# SCH.net
KiCad netlist of a schematic drawn in EasyEDA
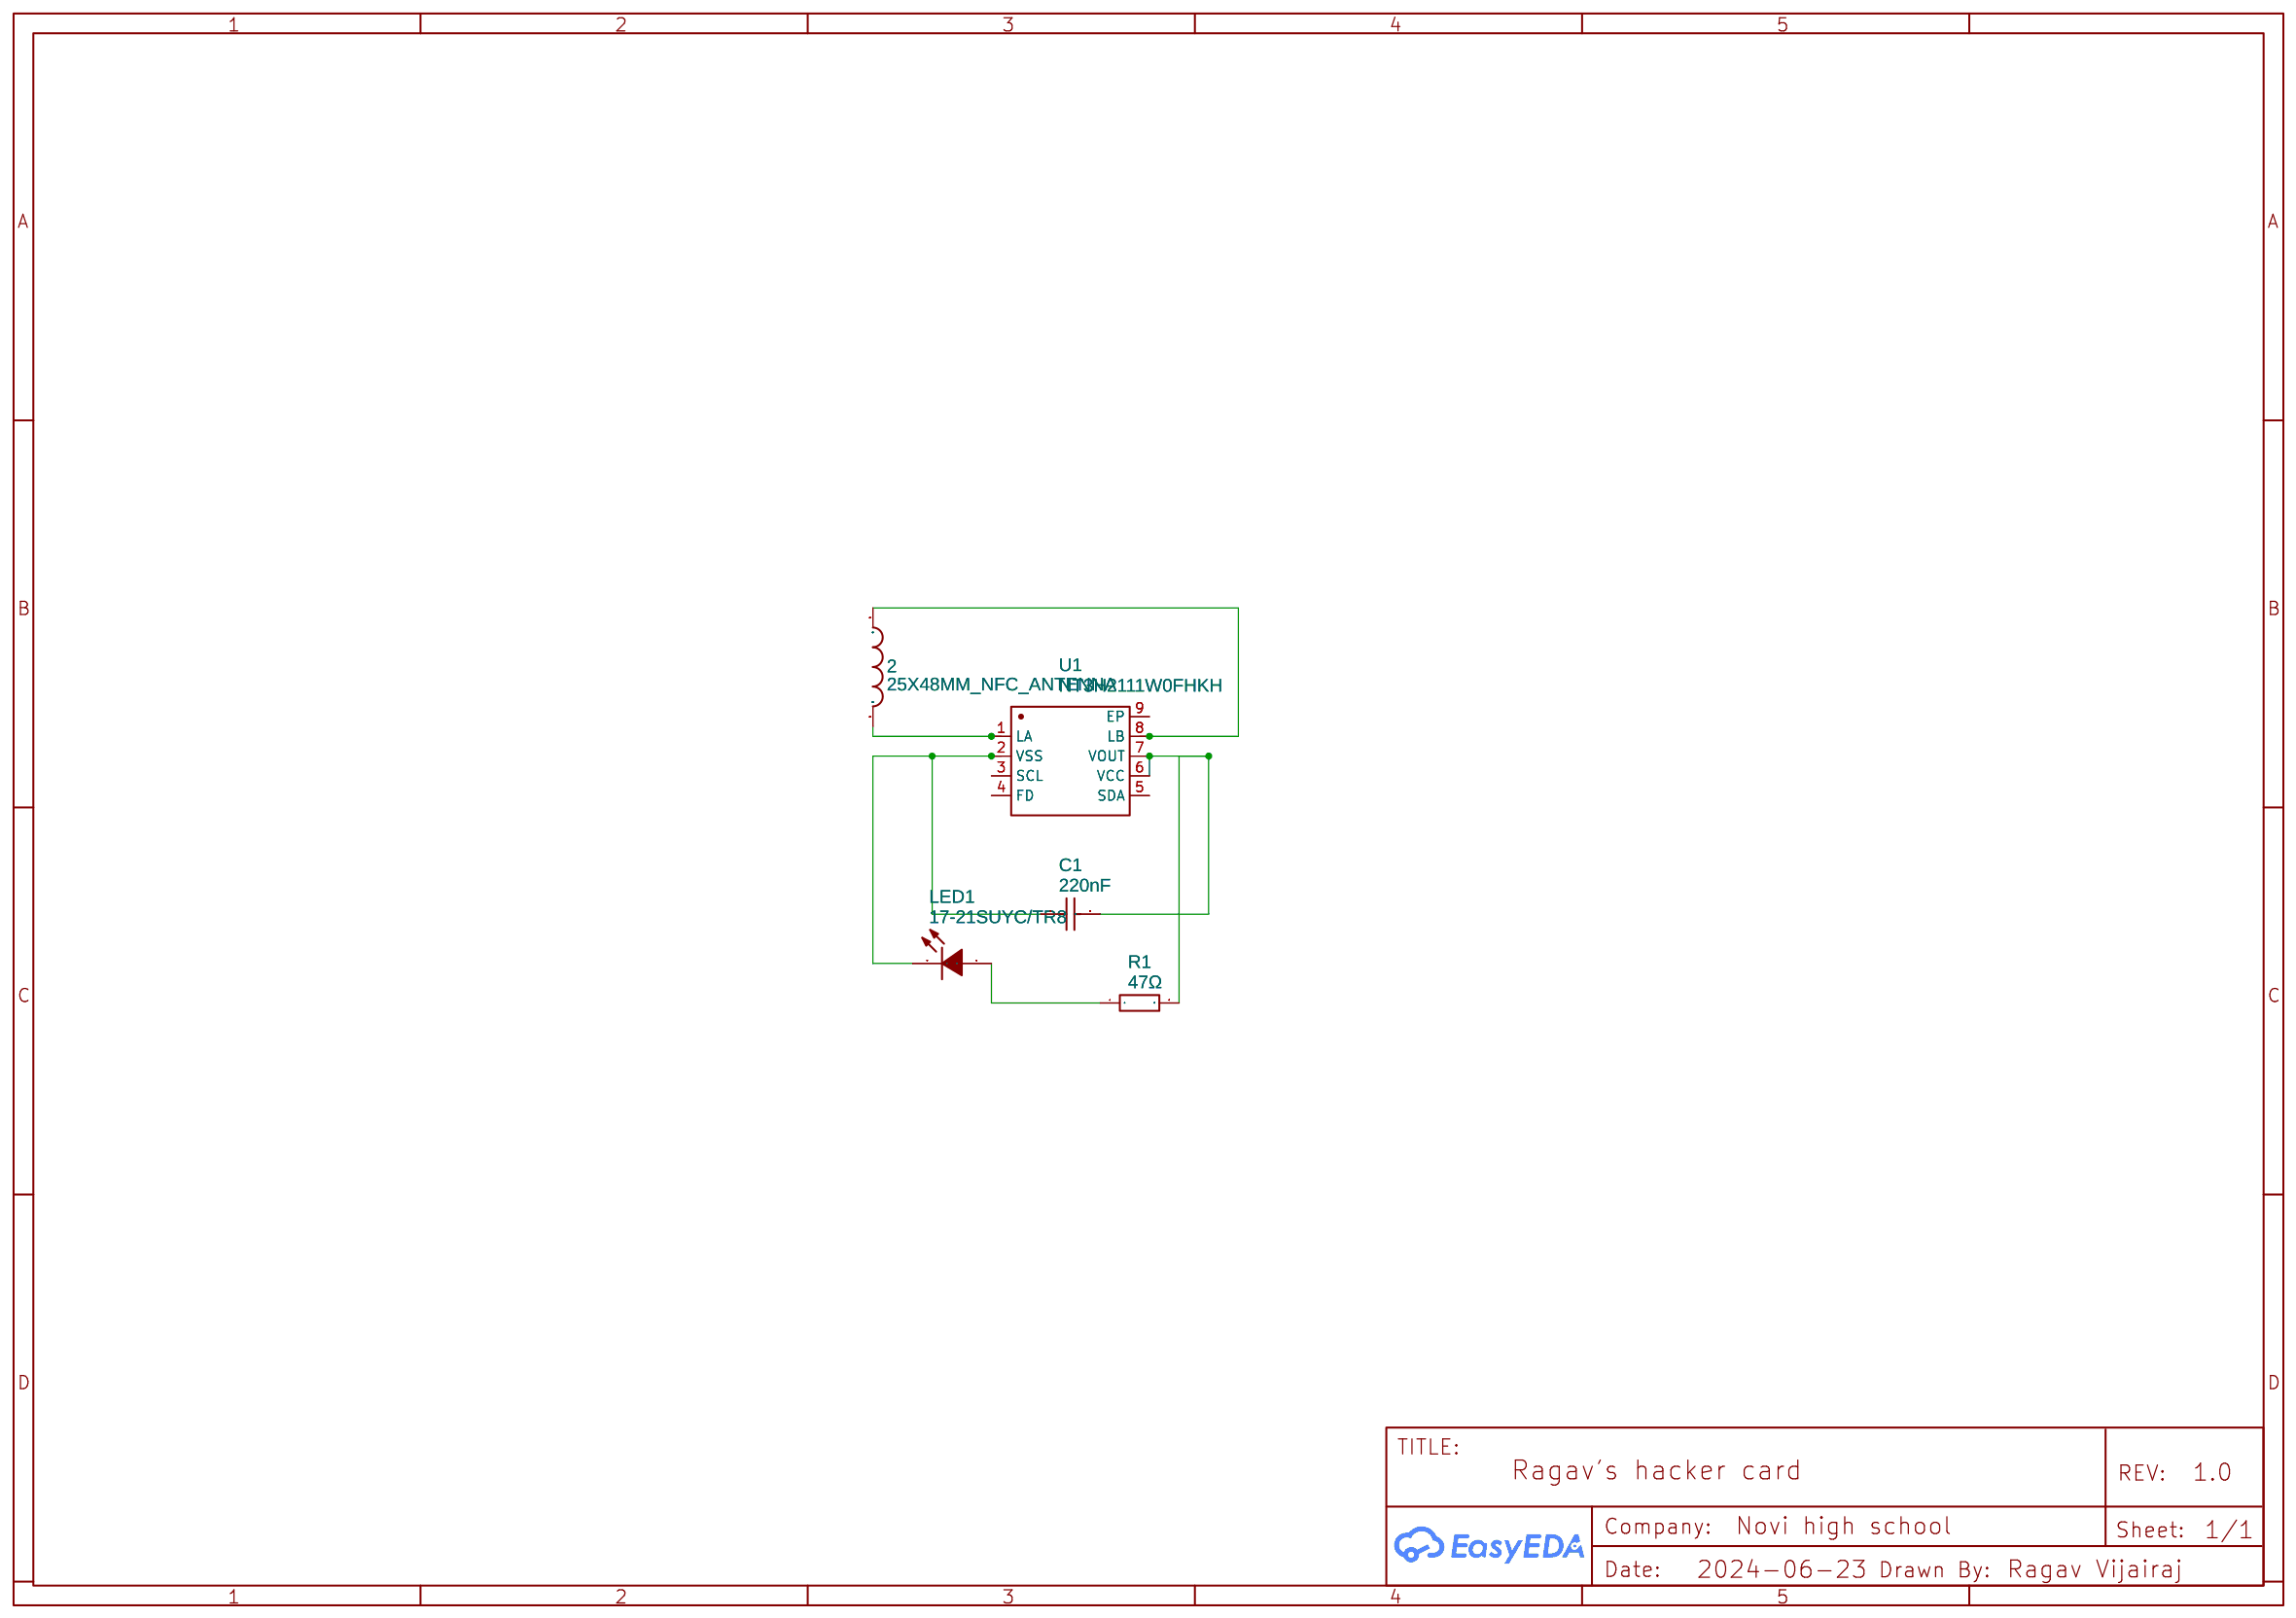
[diagram p0: schematic sheet]

(export (version "E")
  (design (tool "Eeschema 10.0.6"))
  (components
    (comp (ref "2") (value "25X48MM_NFC_ANTENNA") (libsource (lib "") (part "25X48MM_NFC_ANTENNA")))
    (comp (ref "C1")
      (value "220nF")
      (fields
        (field (name "Manufacturer Part") "CL10B224KA8NNNC")
        (field (name "Manufacturer") "SAMSUNG(三星)")
      )
      (libsource (lib "") (part "CL10B224KA8NNNC"))
    )
    (comp (ref "LED1")
      (value "17-21SUYC/TR8")
      (fields (field (name "Manufacturer Part") "KT-0805黄灯") (field (name "Manufacturer") "KENTO"))
      (libsource (lib "") (part "17-21SUYC/TR8"))
    )
    (comp (ref "R1")
      (value "47Ω")
      (fields
        (field (name "Manufacturer Part") "0603WAF470JT5E")
        (field (name "Manufacturer") "UNI-ROYAL(厚声)")
      )
      (libsource (lib "") (part "0603WAF470JT5E"))
    )
    (comp (ref "U1")
      (value "NT3H2111W0FHKH")
      (fields (field (name "Manufacturer") "NXP(恩智浦)"))
      (libsource (lib "") (part "NT3H2111W0FHKH"))
    )
  )
  (nets
    (net (code "1") (name "Net-(LED1-+)") (class "Default")
      (node (ref "LED1") (pin "1") (pinfunction "+_1") (pintype "unspecified"))
      (node (ref "R1") (pin "1") (pinfunction "1_1") (pintype "input"))
    )
    (net (code "2") (name "Net-(LED1--)") (class "Default")
      (node (ref "C1") (pin "1") (pinfunction "1_1") (pintype "input"))
      (node (ref "LED1") (pin "2") (pinfunction "-_2") (pintype "unspecified"))
      (node (ref "U1") (pin "2") (pinfunction "VSS_2") (pintype "unspecified"))
    )
    (net (code "3") (name "Net-(U1-LA)") (class "Default")
      (node (ref "2") (pin "P$2") (pinfunction "P$2_P$2") (pintype "bidirectional"))
      (node (ref "U1") (pin "1") (pinfunction "LA_1") (pintype "unspecified"))
    )
    (net (code "4") (name "Net-(U1-LB)") (class "Default")
      (node (ref "2") (pin "P$1") (pinfunction "P$1_P$1") (pintype "bidirectional"))
      (node (ref "U1") (pin "8") (pinfunction "LB_8") (pintype "unspecified"))
    )
    (net (code "5") (name "Net-(U1-VCC)") (class "Default")
      (node (ref "C1") (pin "2") (pinfunction "2_2") (pintype "input"))
      (node (ref "R1") (pin "2") (pinfunction "2_2") (pintype "input"))
      (node (ref "U1") (pin "6") (pinfunction "VCC_6") (pintype "unspecified"))
      (node (ref "U1") (pin "7") (pinfunction "VOUT_7") (pintype "unspecified"))
    )
    (net (code "6") (name "unconnected-(U1-EP-Pad9)") (class "Default")
      (node (ref "U1") (pin "9") (pinfunction "EP_9") (pintype "unspecified"))
    )
    (net (code "7") (name "unconnected-(U1-FD-Pad4)") (class "Default")
      (node (ref "U1") (pin "4") (pinfunction "FD_4") (pintype "unspecified"))
    )
    (net (code "8") (name "unconnected-(U1-SCL-Pad3)") (class "Default")
      (node (ref "U1") (pin "3") (pinfunction "SCL_3") (pintype "unspecified"))
    )
    (net (code "9") (name "unconnected-(U1-SDA-Pad5)") (class "Default")
      (node (ref "U1") (pin "5") (pinfunction "SDA_5") (pintype "unspecified"))
    )
  )
)
